# oscar_shield.net
KiCad netlist of a schematic drawn in EAGLE
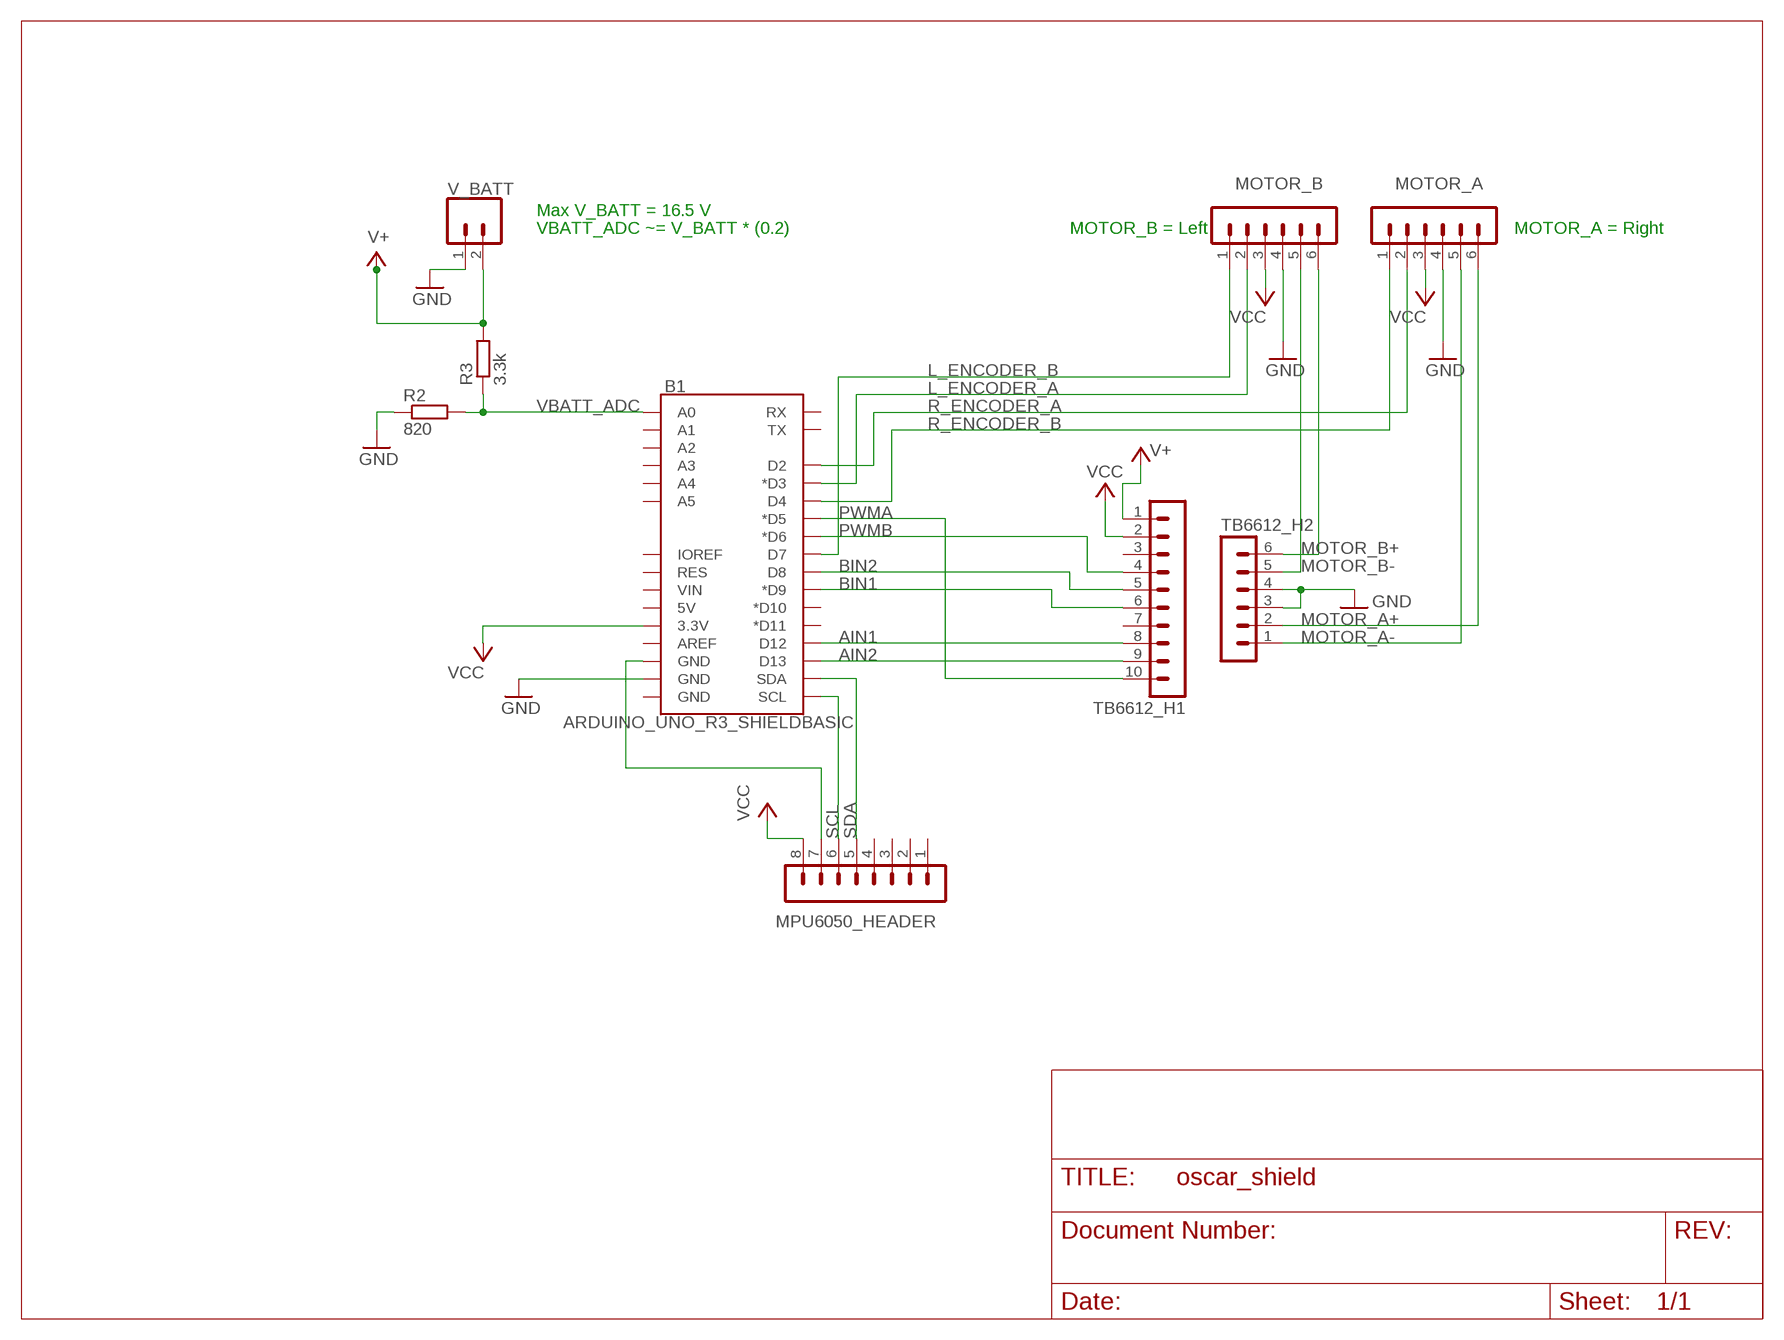
[diagram p0: schematic, sheet 1]

(export (version "E")
  (design (tool "Eeschema 10.0.6"))
  (components
    (comp (ref "B1")
      (value "ARDUINO_UNO_R3_SHIELDBASIC")
      (footprint "eagle-import:UNO_R3_SHIELD")
      (libsource (lib "eagle-import") (part "ARDUINO_UNO_R3_SHIELDBASIC"))
    )
    (comp (ref "MOTOR_A")
      (value "MA06-1")
      (footprint "eagle-import:MA06-1")
      (libsource (lib "eagle-import") (part "MA06-1"))
    )
    (comp (ref "MOTOR_B")
      (value "MA06-1")
      (footprint "eagle-import:MA06-1")
      (libsource (lib "eagle-import") (part "MA06-1"))
    )
    (comp (ref "MPU6050_HEADER")
      (value "MA08-1")
      (footprint "eagle-import:MA08-1")
      (libsource (lib "eagle-import") (part "MA08-1"))
    )
    (comp (ref "R2")
      (value "820")
      (footprint "eagle-import:0207_10")
      (libsource (lib "eagle-import") (part "R-EU_0207/10"))
    )
    (comp (ref "R3")
      (value "3.3k")
      (footprint "eagle-import:0207_10")
      (libsource (lib "eagle-import") (part "R-EU_0207/10"))
    )
    (comp (ref "TB6612_H1")
      (value "MA10-1")
      (footprint "eagle-import:MA10-1")
      (libsource (lib "eagle-import") (part "MA10-1"))
    )
    (comp (ref "TB6612_H2")
      (value "MA06-1")
      (footprint "eagle-import:MA06-1")
      (libsource (lib "eagle-import") (part "MA06-1"))
    )
    (comp (ref "V_BATT")
      (value "CONN_025MM")
      (footprint "eagle-import:SCREWTERMINAL-5MM-2")
      (libsource (lib "eagle-import") (part "CONN_025MM"))
    )
  )
  (nets
    (net (code "1") (name "/AIN1") (class "Default")
      (node (ref "B1") (pin "D12") (pinfunction "D12_D12") (pintype "bidirectional"))
      (node (ref "TB6612_H1") (pin "8") (pinfunction "8_8") (pintype "passive"))
    )
    (net (code "2") (name "/AIN2") (class "Default")
      (node (ref "B1") (pin "D13") (pinfunction "D13_D13") (pintype "bidirectional"))
      (node (ref "TB6612_H1") (pin "9") (pinfunction "9_9") (pintype "passive"))
    )
    (net (code "3") (name "/BIN1") (class "Default")
      (node (ref "B1") (pin "D9") (pinfunction "*D9_D9") (pintype "bidirectional"))
      (node (ref "TB6612_H1") (pin "6") (pinfunction "6_6") (pintype "passive"))
    )
    (net (code "4") (name "/BIN2") (class "Default")
      (node (ref "B1") (pin "D8") (pinfunction "D8_D8") (pintype "bidirectional"))
      (node (ref "TB6612_H1") (pin "5") (pinfunction "5_5") (pintype "passive"))
    )
    (net (code "5") (name "/L_ENCODER_A") (class "Default")
      (node (ref "B1") (pin "D3") (pinfunction "*D3_D3") (pintype "bidirectional"))
      (node (ref "MOTOR_B") (pin "2") (pinfunction "2_2") (pintype "passive"))
    )
    (net (code "6") (name "/L_ENCODER_B") (class "Default")
      (node (ref "B1") (pin "D7") (pinfunction "D7_D7") (pintype "bidirectional"))
      (node (ref "MOTOR_B") (pin "1") (pinfunction "1_1") (pintype "passive"))
    )
    (net (code "7") (name "/MOTOR_A+") (class "Default")
      (node (ref "MOTOR_A") (pin "6") (pinfunction "6_6") (pintype "passive"))
      (node (ref "TB6612_H2") (pin "2") (pinfunction "2_2") (pintype "passive"))
    )
    (net (code "8") (name "/MOTOR_A-") (class "Default")
      (node (ref "MOTOR_A") (pin "5") (pinfunction "5_5") (pintype "passive"))
      (node (ref "TB6612_H2") (pin "1") (pinfunction "1_1") (pintype "passive"))
    )
    (net (code "9") (name "/MOTOR_B+") (class "Default")
      (node (ref "MOTOR_B") (pin "6") (pinfunction "6_6") (pintype "passive"))
      (node (ref "TB6612_H2") (pin "6") (pinfunction "6_6") (pintype "passive"))
    )
    (net (code "10") (name "/MOTOR_B-") (class "Default")
      (node (ref "MOTOR_B") (pin "5") (pinfunction "5_5") (pintype "passive"))
      (node (ref "TB6612_H2") (pin "5") (pinfunction "5_5") (pintype "passive"))
    )
    (net (code "11") (name "/PWMA") (class "Default")
      (node (ref "B1") (pin "D5") (pinfunction "*D5_D5") (pintype "bidirectional"))
      (node (ref "TB6612_H1") (pin "10") (pinfunction "10_10") (pintype "passive"))
    )
    (net (code "12") (name "/PWMB") (class "Default")
      (node (ref "B1") (pin "D6") (pinfunction "*D6_D6") (pintype "bidirectional"))
      (node (ref "TB6612_H1") (pin "4") (pinfunction "4_4") (pintype "passive"))
    )
    (net (code "13") (name "/R_ENCODER_A") (class "Default")
      (node (ref "B1") (pin "D2") (pinfunction "D2_D2") (pintype "bidirectional"))
      (node (ref "MOTOR_A") (pin "2") (pinfunction "2_2") (pintype "passive"))
    )
    (net (code "14") (name "/R_ENCODER_B") (class "Default")
      (node (ref "B1") (pin "D4") (pinfunction "D4_D4") (pintype "bidirectional"))
      (node (ref "MOTOR_A") (pin "1") (pinfunction "1_1") (pintype "passive"))
    )
    (net (code "15") (name "/SCL") (class "Default")
      (node (ref "B1") (pin "SCL") (pinfunction "SCL_SCL") (pintype "bidirectional"))
      (node (ref "MPU6050_HEADER") (pin "6") (pinfunction "6_6") (pintype "passive"))
    )
    (net (code "16") (name "/SDA") (class "Default")
      (node (ref "B1") (pin "SDA") (pinfunction "SDA_SDA") (pintype "bidirectional"))
      (node (ref "MPU6050_HEADER") (pin "5") (pinfunction "5_5") (pintype "passive"))
    )
    (net (code "17") (name "/VBATT_ADC") (class "Default")
      (node (ref "B1") (pin "A0") (pinfunction "A0_A0") (pintype "bidirectional"))
      (node (ref "R2") (pin "2") (pinfunction "2_2") (pintype "passive"))
      (node (ref "R3") (pin "1") (pinfunction "1_1") (pintype "passive"))
    )
    (net (code "18") (name "GND") (class "Default")
      (node (ref "B1") (pin "GND@1") (pinfunction "GND_GND@1") (pintype "bidirectional"))
      (node (ref "MOTOR_A") (pin "4") (pinfunction "4_4") (pintype "passive"))
      (node (ref "MOTOR_B") (pin "4") (pinfunction "4_4") (pintype "passive"))
      (node (ref "R2") (pin "1") (pinfunction "1_1") (pintype "passive"))
      (node (ref "TB6612_H2") (pin "3") (pinfunction "3_3") (pintype "passive"))
      (node (ref "TB6612_H2") (pin "4") (pinfunction "4_4") (pintype "passive"))
      (node (ref "V_BATT") (pin "1") (pinfunction "1_1") (pintype "passive"))
    )
    (net (code "19") (name "Net-(B1-GND-PadGND@2)") (class "Default")
      (node (ref "B1") (pin "GND@2") (pinfunction "GND_GND@2") (pintype "bidirectional"))
      (node (ref "MPU6050_HEADER") (pin "7") (pinfunction "7_7") (pintype "passive"))
    )
    (net (code "20") (name "V+") (class "Default")
      (node (ref "R3") (pin "2") (pinfunction "2_2") (pintype "passive"))
      (node (ref "TB6612_H1") (pin "1") (pinfunction "1_1") (pintype "passive"))
      (node (ref "V_BATT") (pin "2") (pinfunction "2_2") (pintype "passive"))
    )
    (net (code "21") (name "VCC") (class "Default")
      (node (ref "B1") (pin "3.3V") (pinfunction "3.3V_3.3V") (pintype "bidirectional"))
      (node (ref "MOTOR_A") (pin "3") (pinfunction "3_3") (pintype "passive"))
      (node (ref "MOTOR_B") (pin "3") (pinfunction "3_3") (pintype "passive"))
      (node (ref "MPU6050_HEADER") (pin "8") (pinfunction "8_8") (pintype "passive"))
      (node (ref "TB6612_H1") (pin "2") (pinfunction "2_2") (pintype "passive"))
    )
    (net (code "22") (name "unconnected-(B1-*D10-PadD10)") (class "Default")
      (node (ref "B1") (pin "D10") (pinfunction "*D10_D10") (pintype "bidirectional"))
    )
    (net (code "23") (name "unconnected-(B1-*D11-PadD11)") (class "Default")
      (node (ref "B1") (pin "D11") (pinfunction "*D11_D11") (pintype "bidirectional"))
    )
    (net (code "24") (name "unconnected-(B1-GND-PadGND@0)") (class "Default")
      (node (ref "B1") (pin "GND@0") (pinfunction "GND_GND@0") (pintype "bidirectional"))
    )
    (net (code "25") (name "unconnected-(B1-Pad5V)") (class "Default")
      (node (ref "B1") (pin "5V") (pinfunction "5V_5V") (pintype "bidirectional"))
    )
    (net (code "26") (name "unconnected-(B1-PadA1)") (class "Default")
      (node (ref "B1") (pin "A1") (pinfunction "A1_A1") (pintype "bidirectional"))
    )
    (net (code "27") (name "unconnected-(B1-PadA2)") (class "Default")
      (node (ref "B1") (pin "A2") (pinfunction "A2_A2") (pintype "bidirectional"))
    )
    (net (code "28") (name "unconnected-(B1-PadA3)") (class "Default")
      (node (ref "B1") (pin "A3") (pinfunction "A3_A3") (pintype "bidirectional"))
    )
    (net (code "29") (name "unconnected-(B1-PadA4)") (class "Default")
      (node (ref "B1") (pin "A4") (pinfunction "A4_A4") (pintype "bidirectional"))
    )
    (net (code "30") (name "unconnected-(B1-PadA5)") (class "Default")
      (node (ref "B1") (pin "A5") (pinfunction "A5_A5") (pintype "bidirectional"))
    )
    (net (code "31") (name "unconnected-(B1-PadAREF)") (class "Default")
      (node (ref "B1") (pin "AREF") (pinfunction "AREF_AREF") (pintype "bidirectional"))
    )
    (net (code "32") (name "unconnected-(B1-PadIOREF)") (class "Default")
      (node (ref "B1") (pin "IOREF") (pinfunction "IOREF_IOREF") (pintype "bidirectional"))
    )
    (net (code "33") (name "unconnected-(B1-PadRES)") (class "Default")
      (node (ref "B1") (pin "RES") (pinfunction "RES_RES") (pintype "bidirectional"))
    )
    (net (code "34") (name "unconnected-(B1-PadRX)") (class "Default")
      (node (ref "B1") (pin "RX") (pinfunction "RX_RX") (pintype "bidirectional"))
    )
    (net (code "35") (name "unconnected-(B1-PadTX)") (class "Default")
      (node (ref "B1") (pin "TX") (pinfunction "TX_TX") (pintype "bidirectional"))
    )
    (net (code "36") (name "unconnected-(B1-PadVIN)") (class "Default")
      (node (ref "B1") (pin "VIN") (pinfunction "VIN_VIN") (pintype "bidirectional"))
    )
    (net (code "37") (name "unconnected-(MPU6050_HEADER-Pad1)") (class "Default")
      (node (ref "MPU6050_HEADER") (pin "1") (pinfunction "1_1") (pintype "passive"))
    )
    (net (code "38") (name "unconnected-(MPU6050_HEADER-Pad2)") (class "Default")
      (node (ref "MPU6050_HEADER") (pin "2") (pinfunction "2_2") (pintype "passive"))
    )
    (net (code "39") (name "unconnected-(MPU6050_HEADER-Pad3)") (class "Default")
      (node (ref "MPU6050_HEADER") (pin "3") (pinfunction "3_3") (pintype "passive"))
    )
    (net (code "40") (name "unconnected-(MPU6050_HEADER-Pad4)") (class "Default")
      (node (ref "MPU6050_HEADER") (pin "4") (pinfunction "4_4") (pintype "passive"))
    )
    (net (code "41") (name "unconnected-(TB6612_H1-Pad3)") (class "Default")
      (node (ref "TB6612_H1") (pin "3") (pinfunction "3_3") (pintype "passive"))
    )
    (net (code "42") (name "unconnected-(TB6612_H1-Pad7)") (class "Default")
      (node (ref "TB6612_H1") (pin "7") (pinfunction "7_7") (pintype "passive"))
    )
  )
)
